# Arduino_Connection_PCB.net
KiCad netlist of a schematic drawn in EAGLE
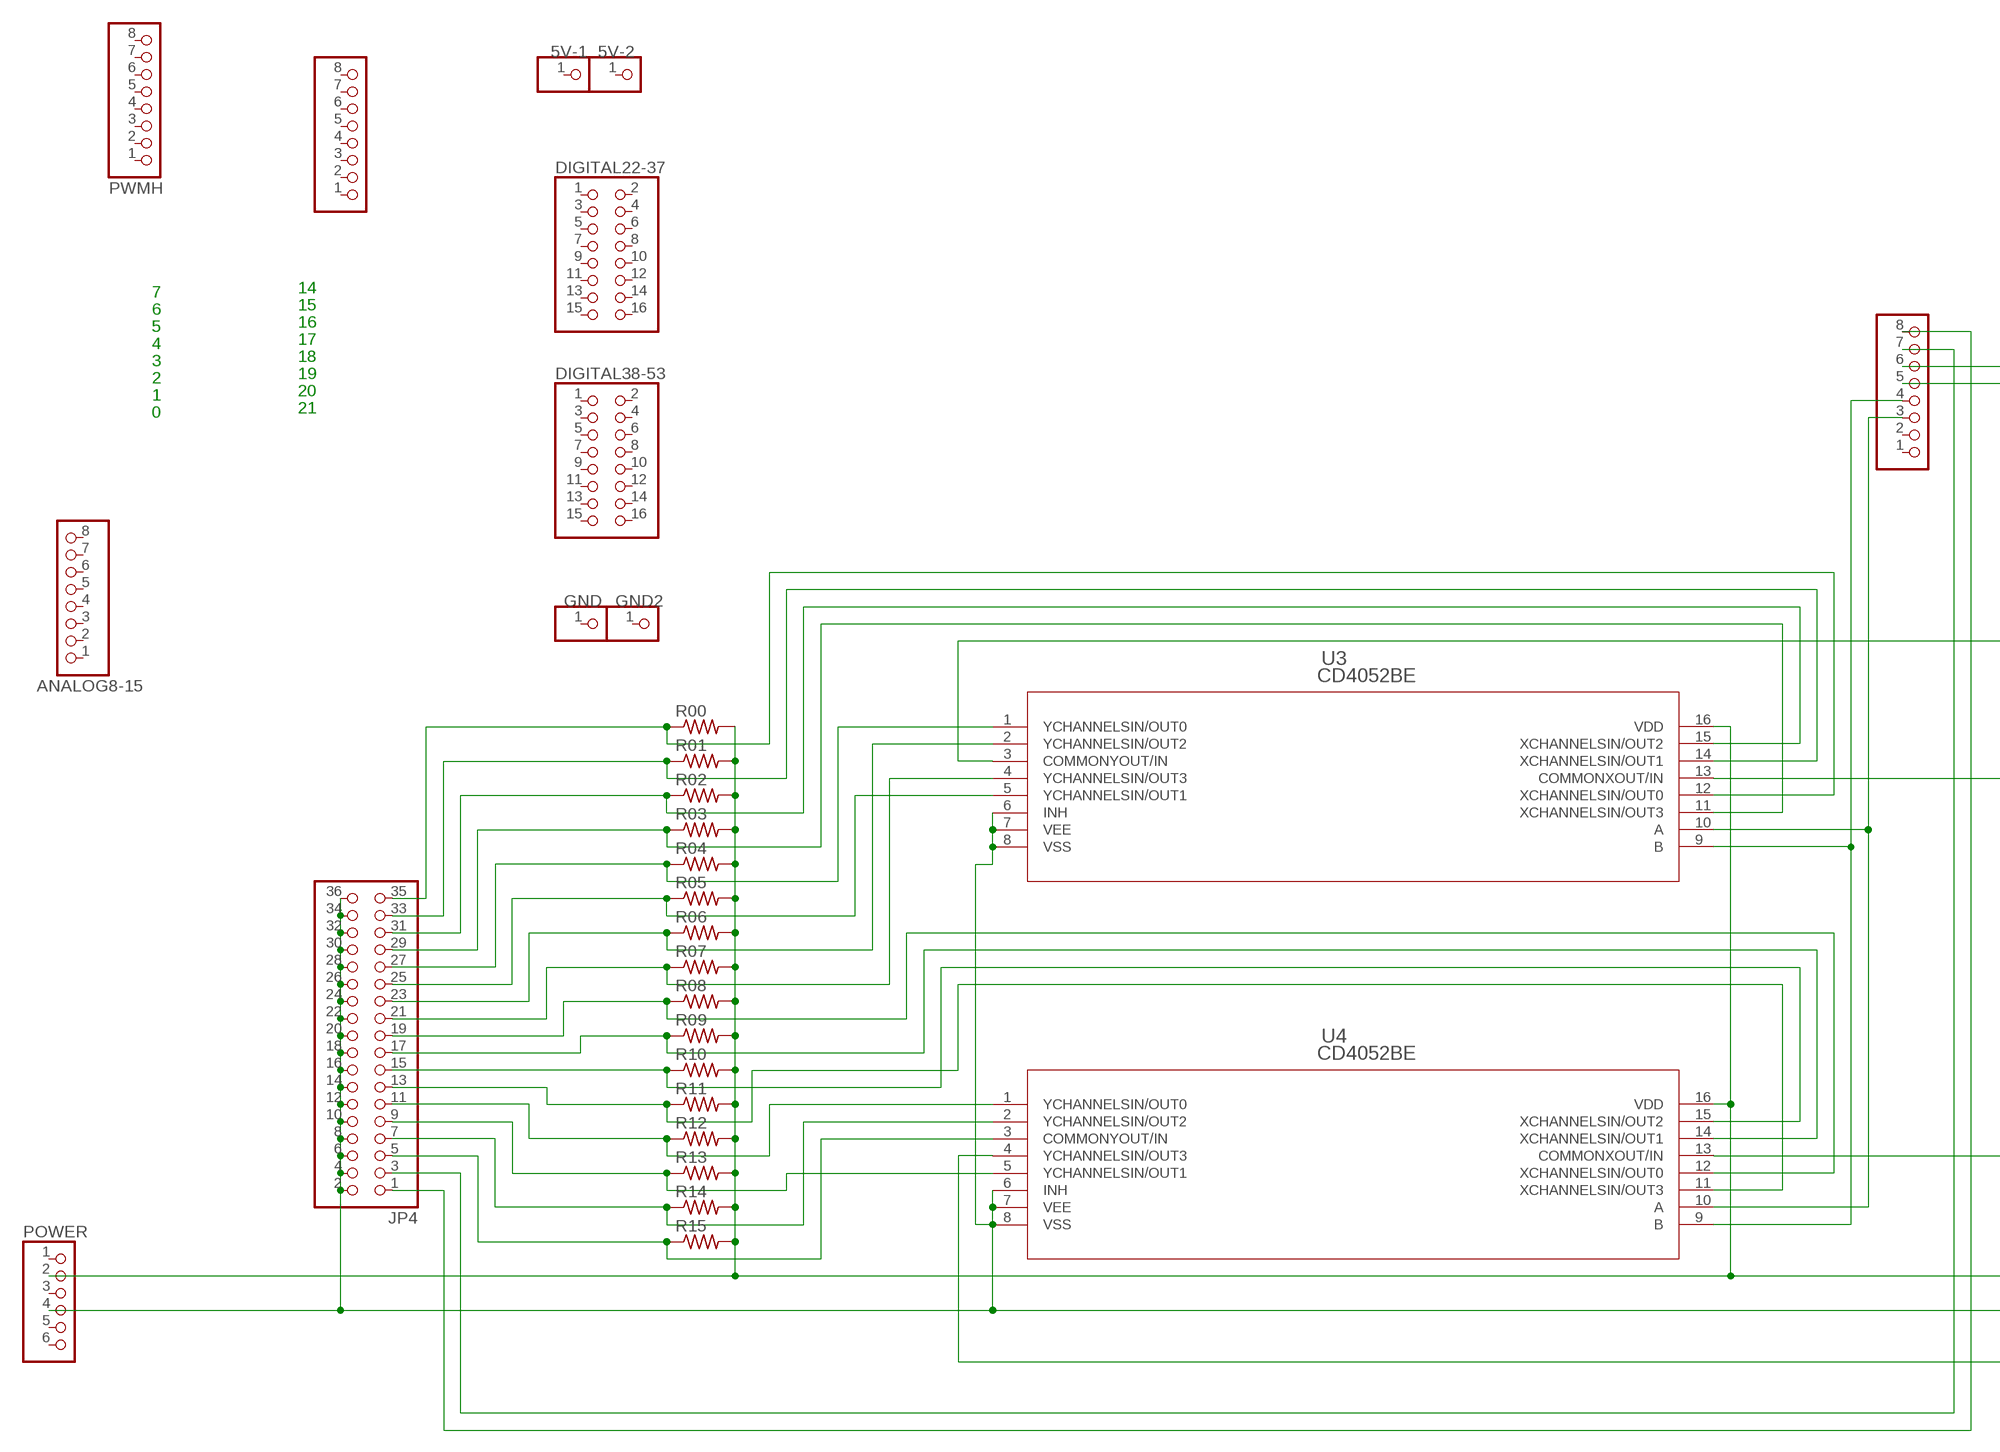
[diagram p0: schematic, sheet 1, part 1 of 2]
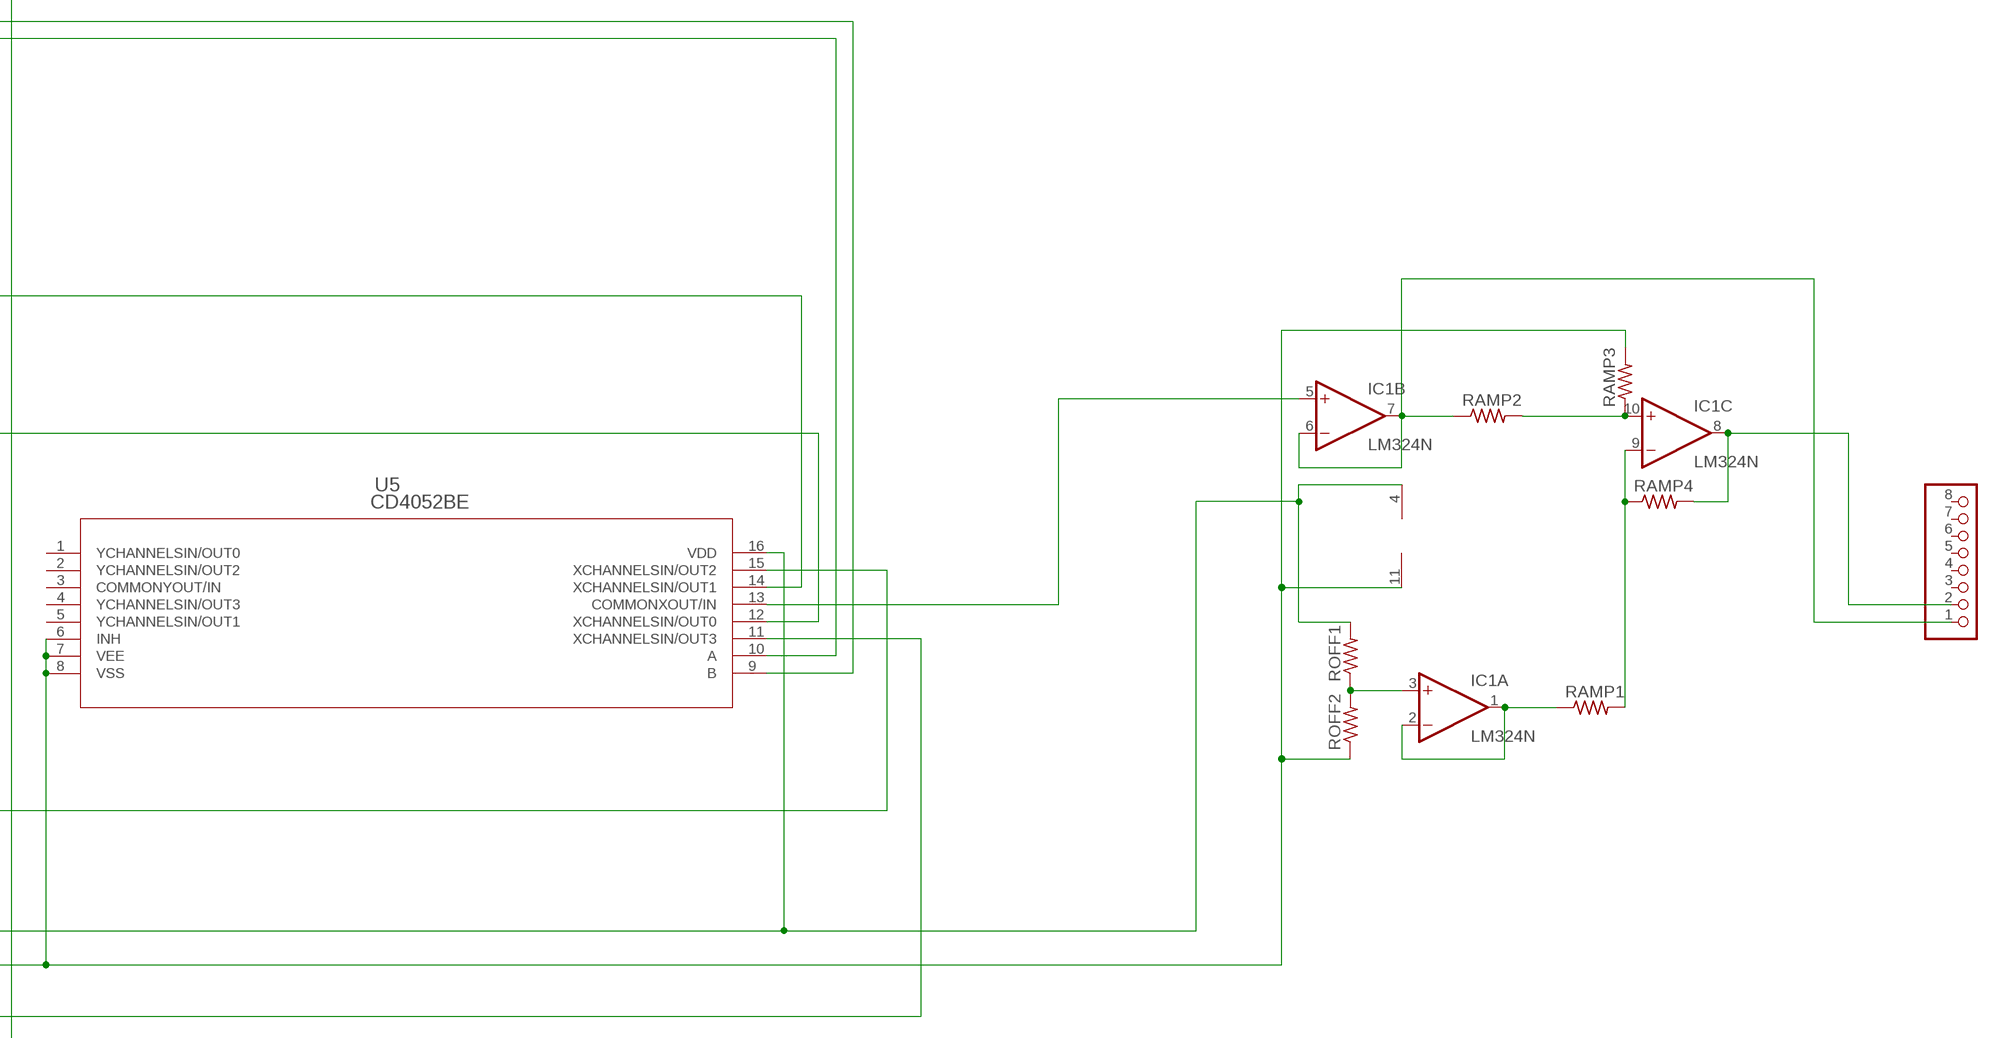
[diagram p1: schematic, sheet 1, part 2 of 2]

(export (version "E")
  (design (tool "Eeschema 10.0.6"))
  (components
    (comp (ref "5V-1")
      (value "PINHD-1X1")
      (footprint "eagle-import:1X01")
      (libsource (lib "eagle-import") (part "PINHD-1X1"))
    )
    (comp (ref "5V-2")
      (value "PINHD-1X1")
      (footprint "eagle-import:1X01")
      (libsource (lib "eagle-import") (part "PINHD-1X1"))
    )
    (comp (ref "ANALOG0-7")
      (value "PINHD-1X8")
      (footprint "eagle-import:1X08")
      (libsource (lib "eagle-import") (part "PINHD-1X8"))
    )
    (comp (ref "ANALOG8-15")
      (value "PINHD-1X8")
      (footprint "eagle-import:1X08")
      (libsource (lib "eagle-import") (part "PINHD-1X8"))
    )
    (comp (ref "COMMUNICATION")
      (value "PINHD-1X8")
      (footprint "eagle-import:1X08")
      (libsource (lib "eagle-import") (part "PINHD-1X8"))
    )
    (comp (ref "DIGITAL22-37")
      (value "PINHD-2X8")
      (footprint "eagle-import:2X08")
      (libsource (lib "eagle-import") (part "PINHD-2X8"))
    )
    (comp (ref "DIGITAL38-53")
      (value "PINHD-2X8")
      (footprint "eagle-import:2X08")
      (libsource (lib "eagle-import") (part "PINHD-2X8"))
    )
    (comp (ref "GND")
      (value "PINHD-1X1")
      (footprint "eagle-import:1X01")
      (libsource (lib "eagle-import") (part "PINHD-1X1"))
    )
    (comp (ref "GND2")
      (value "PINHD-1X1")
      (footprint "eagle-import:1X01")
      (libsource (lib "eagle-import") (part "PINHD-1X1"))
    )
    (comp (ref "IC1")
      (value "LM324N")
      (footprint "eagle-import:DIL14")
      (libsource (lib "eagle-import") (part "LM324N"))
    )
    (comp (ref "JP4")
      (value "PINHD-2X18/90")
      (footprint "eagle-import:2X18_90")
      (libsource (lib "eagle-import") (part "PINHD-2X18/90"))
    )
    (comp (ref "POWER")
      (value "PINHD-1X6")
      (footprint "eagle-import:1X06")
      (libsource (lib "eagle-import") (part "PINHD-1X6"))
    )
    (comp (ref "PWMH")
      (value "PINHD-1X8")
      (footprint "eagle-import:1X08")
      (libsource (lib "eagle-import") (part "PINHD-1X8"))
    )
    (comp (ref "PWML")
      (value "PINHD-1X8")
      (footprint "eagle-import:1X08")
      (libsource (lib "eagle-import") (part "PINHD-1X8"))
    )
    (comp (ref "R00")
      (value "R-US_0204/7")
      (footprint "eagle-import:0204_7")
      (libsource (lib "eagle-import") (part "R-US_0204/7"))
    )
    (comp (ref "R01")
      (value "R-US_0204/7")
      (footprint "eagle-import:0204_7")
      (libsource (lib "eagle-import") (part "R-US_0204/7"))
    )
    (comp (ref "R02")
      (value "R-US_0204/7")
      (footprint "eagle-import:0204_7")
      (libsource (lib "eagle-import") (part "R-US_0204/7"))
    )
    (comp (ref "R03")
      (value "R-US_0204/7")
      (footprint "eagle-import:0204_7")
      (libsource (lib "eagle-import") (part "R-US_0204/7"))
    )
    (comp (ref "R04")
      (value "R-US_0204/7")
      (footprint "eagle-import:0204_7")
      (libsource (lib "eagle-import") (part "R-US_0204/7"))
    )
    (comp (ref "R05")
      (value "R-US_0204/7")
      (footprint "eagle-import:0204_7")
      (libsource (lib "eagle-import") (part "R-US_0204/7"))
    )
    (comp (ref "R06")
      (value "R-US_0204/7")
      (footprint "eagle-import:0204_7")
      (libsource (lib "eagle-import") (part "R-US_0204/7"))
    )
    (comp (ref "R07")
      (value "R-US_0204/7")
      (footprint "eagle-import:0204_7")
      (libsource (lib "eagle-import") (part "R-US_0204/7"))
    )
    (comp (ref "R08")
      (value "R-US_0204/7")
      (footprint "eagle-import:0204_7")
      (libsource (lib "eagle-import") (part "R-US_0204/7"))
    )
    (comp (ref "R09")
      (value "R-US_0204/7")
      (footprint "eagle-import:0204_7")
      (libsource (lib "eagle-import") (part "R-US_0204/7"))
    )
    (comp (ref "R10")
      (value "R-US_0204/7")
      (footprint "eagle-import:0204_7")
      (libsource (lib "eagle-import") (part "R-US_0204/7"))
    )
    (comp (ref "R11")
      (value "R-US_0204/7")
      (footprint "eagle-import:0204_7")
      (libsource (lib "eagle-import") (part "R-US_0204/7"))
    )
    (comp (ref "R12")
      (value "R-US_0204/7")
      (footprint "eagle-import:0204_7")
      (libsource (lib "eagle-import") (part "R-US_0204/7"))
    )
    (comp (ref "R13")
      (value "R-US_0204/7")
      (footprint "eagle-import:0204_7")
      (libsource (lib "eagle-import") (part "R-US_0204/7"))
    )
    (comp (ref "R14")
      (value "R-US_0204/7")
      (footprint "eagle-import:0204_7")
      (libsource (lib "eagle-import") (part "R-US_0204/7"))
    )
    (comp (ref "R15")
      (value "R-US_0204/7")
      (footprint "eagle-import:0204_7")
      (libsource (lib "eagle-import") (part "R-US_0204/7"))
    )
    (comp (ref "RAMP1")
      (value "R-US_0204/7")
      (footprint "eagle-import:0204_7")
      (libsource (lib "eagle-import") (part "R-US_0204/7"))
    )
    (comp (ref "RAMP2")
      (value "R-US_0204/7")
      (footprint "eagle-import:0204_7")
      (libsource (lib "eagle-import") (part "R-US_0204/7"))
    )
    (comp (ref "RAMP3")
      (value "R-US_0204/7")
      (footprint "eagle-import:0204_7")
      (libsource (lib "eagle-import") (part "R-US_0204/7"))
    )
    (comp (ref "RAMP4")
      (value "R-US_0204/7")
      (footprint "eagle-import:0204_7")
      (libsource (lib "eagle-import") (part "R-US_0204/7"))
    )
    (comp (ref "ROFF1")
      (value "R-US_0204/7")
      (footprint "eagle-import:0204_7")
      (libsource (lib "eagle-import") (part "R-US_0204/7"))
    )
    (comp (ref "ROFF2")
      (value "R-US_0204/7")
      (footprint "eagle-import:0204_7")
      (libsource (lib "eagle-import") (part "R-US_0204/7"))
    )
    (comp (ref "U3")
      (value "CD4052BE")
      (footprint "eagle-import:N16")
      (libsource (lib "eagle-import") (part "CD4052BE"))
    )
    (comp (ref "U4")
      (value "CD4052BE")
      (footprint "eagle-import:N16")
      (libsource (lib "eagle-import") (part "CD4052BE"))
    )
    (comp (ref "U5")
      (value "CD4052BE")
      (footprint "eagle-import:N16")
      (libsource (lib "eagle-import") (part "CD4052BE"))
    )
  )
  (nets
    (net (code "1") (name "Net-(IC1A-+IN)") (class "Default")
      (node (ref "IC1") (pin "3") (pinfunction "+IN_3") (pintype "input"))
      (node (ref "ROFF1") (pin "1") (pinfunction "1_1") (pintype "passive"))
      (node (ref "ROFF2") (pin "2") (pinfunction "2_2") (pintype "passive"))
    )
    (net (code "2") (name "Net-(IC1A--IN)") (class "Default")
      (node (ref "IC1") (pin "1") (pinfunction "OUT_1") (pintype "output"))
      (node (ref "IC1") (pin "2") (pinfunction "-IN_2") (pintype "input"))
      (node (ref "RAMP1") (pin "1") (pinfunction "1_1") (pintype "passive"))
    )
    (net (code "3") (name "Net-(IC1B-+IN)") (class "Default")
      (node (ref "IC1") (pin "5") (pinfunction "+IN_5") (pintype "input"))
      (node (ref "U5") (pin "13") (pinfunction "COMMONXOUT/IN_13") (pintype "bidirectional"))
    )
    (net (code "4") (name "Net-(IC1B--IN)") (class "Default")
      (node (ref "ANALOG0-7") (pin "1") (pinfunction "1_1") (pintype "passive"))
      (node (ref "IC1") (pin "6") (pinfunction "-IN_6") (pintype "input"))
      (node (ref "IC1") (pin "7") (pinfunction "OUT_7") (pintype "output"))
      (node (ref "RAMP2") (pin "1") (pinfunction "1_1") (pintype "passive"))
    )
    (net (code "5") (name "Net-(IC1C-+IN)") (class "Default")
      (node (ref "IC1") (pin "10") (pinfunction "+IN_10") (pintype "input"))
      (node (ref "RAMP2") (pin "2") (pinfunction "2_2") (pintype "passive"))
      (node (ref "RAMP3") (pin "1") (pinfunction "1_1") (pintype "passive"))
    )
    (net (code "6") (name "Net-(IC1C--IN)") (class "Default")
      (node (ref "IC1") (pin "9") (pinfunction "-IN_9") (pintype "input"))
      (node (ref "RAMP1") (pin "2") (pinfunction "2_2") (pintype "passive"))
      (node (ref "RAMP4") (pin "1") (pinfunction "1_1") (pintype "passive"))
    )
    (net (code "7") (name "Net-(IC1C-OUT)") (class "Default")
      (node (ref "ANALOG0-7") (pin "2") (pinfunction "2_2") (pintype "passive"))
      (node (ref "IC1") (pin "8") (pinfunction "OUT_8") (pintype "output"))
      (node (ref "RAMP4") (pin "2") (pinfunction "2_2") (pintype "passive"))
    )
    (net (code "8") (name "Net-(IC1E-V+)") (class "Default")
      (node (ref "IC1") (pin "4") (pinfunction "V+_4") (pintype "power_in"))
      (node (ref "POWER") (pin "2") (pinfunction "2_2") (pintype "passive"))
      (node (ref "R00") (pin "2") (pinfunction "2_2") (pintype "passive"))
      (node (ref "R01") (pin "2") (pinfunction "2_2") (pintype "passive"))
      (node (ref "R02") (pin "2") (pinfunction "2_2") (pintype "passive"))
      (node (ref "R03") (pin "2") (pinfunction "2_2") (pintype "passive"))
      (node (ref "R04") (pin "2") (pinfunction "2_2") (pintype "passive"))
      (node (ref "R05") (pin "2") (pinfunction "2_2") (pintype "passive"))
      (node (ref "R06") (pin "2") (pinfunction "2_2") (pintype "passive"))
      (node (ref "R07") (pin "2") (pinfunction "2_2") (pintype "passive"))
      (node (ref "R08") (pin "2") (pinfunction "2_2") (pintype "passive"))
      (node (ref "R09") (pin "2") (pinfunction "2_2") (pintype "passive"))
      (node (ref "R10") (pin "2") (pinfunction "2_2") (pintype "passive"))
      (node (ref "R11") (pin "2") (pinfunction "2_2") (pintype "passive"))
      (node (ref "R12") (pin "2") (pinfunction "2_2") (pintype "passive"))
      (node (ref "R13") (pin "2") (pinfunction "2_2") (pintype "passive"))
      (node (ref "R14") (pin "2") (pinfunction "2_2") (pintype "passive"))
      (node (ref "R15") (pin "2") (pinfunction "2_2") (pintype "passive"))
      (node (ref "ROFF1") (pin "2") (pinfunction "2_2") (pintype "passive"))
      (node (ref "U3") (pin "16") (pinfunction "VDD_16") (pintype "power_in"))
      (node (ref "U4") (pin "16") (pinfunction "VDD_16") (pintype "power_in"))
      (node (ref "U5") (pin "16") (pinfunction "VDD_16") (pintype "power_in"))
    )
    (net (code "9") (name "Net-(IC1E-V-)") (class "Default")
      (node (ref "IC1") (pin "11") (pinfunction "V-_11") (pintype "power_in"))
      (node (ref "JP4") (pin "10") (pinfunction "10_10") (pintype "passive"))
      (node (ref "JP4") (pin "12") (pinfunction "12_12") (pintype "passive"))
      (node (ref "JP4") (pin "14") (pinfunction "14_14") (pintype "passive"))
      (node (ref "JP4") (pin "16") (pinfunction "16_16") (pintype "passive"))
      (node (ref "JP4") (pin "18") (pinfunction "18_18") (pintype "passive"))
      (node (ref "JP4") (pin "2") (pinfunction "2_2") (pintype "passive"))
      (node (ref "JP4") (pin "20") (pinfunction "20_20") (pintype "passive"))
      (node (ref "JP4") (pin "22") (pinfunction "22_22") (pintype "passive"))
      (node (ref "JP4") (pin "24") (pinfunction "24_24") (pintype "passive"))
      (node (ref "JP4") (pin "26") (pinfunction "26_26") (pintype "passive"))
      (node (ref "JP4") (pin "28") (pinfunction "28_28") (pintype "passive"))
      (node (ref "JP4") (pin "30") (pinfunction "30_30") (pintype "passive"))
      (node (ref "JP4") (pin "32") (pinfunction "32_32") (pintype "passive"))
      (node (ref "JP4") (pin "34") (pinfunction "34_34") (pintype "passive"))
      (node (ref "JP4") (pin "36") (pinfunction "36_36") (pintype "passive"))
      (node (ref "JP4") (pin "4") (pinfunction "4_4") (pintype "passive"))
      (node (ref "JP4") (pin "6") (pinfunction "6_6") (pintype "passive"))
      (node (ref "JP4") (pin "8") (pinfunction "8_8") (pintype "passive"))
      (node (ref "POWER") (pin "4") (pinfunction "4_4") (pintype "passive"))
      (node (ref "RAMP3") (pin "2") (pinfunction "2_2") (pintype "passive"))
      (node (ref "ROFF2") (pin "1") (pinfunction "1_1") (pintype "passive"))
      (node (ref "U3") (pin "6") (pinfunction "INH_6") (pintype "passive"))
      (node (ref "U3") (pin "7") (pinfunction "VEE_7") (pintype "power_in"))
      (node (ref "U3") (pin "8") (pinfunction "VSS_8") (pintype "power_in"))
      (node (ref "U4") (pin "6") (pinfunction "INH_6") (pintype "passive"))
      (node (ref "U4") (pin "7") (pinfunction "VEE_7") (pintype "power_in"))
      (node (ref "U4") (pin "8") (pinfunction "VSS_8") (pintype "power_in"))
      (node (ref "U5") (pin "6") (pinfunction "INH_6") (pintype "passive"))
      (node (ref "U5") (pin "7") (pinfunction "VEE_7") (pintype "power_in"))
      (node (ref "U5") (pin "8") (pinfunction "VSS_8") (pintype "power_in"))
    )
    (net (code "10") (name "Net-(JP4-Pad1)") (class "Default")
      (node (ref "JP4") (pin "1") (pinfunction "1_1") (pintype "passive"))
      (node (ref "PWML") (pin "8") (pinfunction "8_8") (pintype "passive"))
    )
    (net (code "11") (name "Net-(JP4-Pad3)") (class "Default")
      (node (ref "JP4") (pin "3") (pinfunction "3_3") (pintype "passive"))
      (node (ref "PWML") (pin "7") (pinfunction "7_7") (pintype "passive"))
    )
    (net (code "12") (name "Net-(U3-A)") (class "Default")
      (node (ref "PWML") (pin "3") (pinfunction "3_3") (pintype "passive"))
      (node (ref "U3") (pin "10") (pinfunction "A_10") (pintype "passive"))
      (node (ref "U4") (pin "10") (pinfunction "A_10") (pintype "passive"))
    )
    (net (code "13") (name "Net-(U3-B)") (class "Default")
      (node (ref "PWML") (pin "4") (pinfunction "4_4") (pintype "passive"))
      (node (ref "U3") (pin "9") (pinfunction "B_9") (pintype "passive"))
      (node (ref "U4") (pin "9") (pinfunction "B_9") (pintype "passive"))
    )
    (net (code "14") (name "Net-(U3-COMMONXOUT{slash}IN)") (class "Default")
      (node (ref "U3") (pin "13") (pinfunction "COMMONXOUT/IN_13") (pintype "bidirectional"))
      (node (ref "U5") (pin "12") (pinfunction "XCHANNELSIN/OUT0_12") (pintype "bidirectional"))
    )
    (net (code "15") (name "Net-(U3-COMMONYOUT{slash}IN)") (class "Default")
      (node (ref "U3") (pin "3") (pinfunction "COMMONYOUT/IN_3") (pintype "bidirectional"))
      (node (ref "U5") (pin "14") (pinfunction "XCHANNELSIN/OUT1_14") (pintype "bidirectional"))
    )
    (net (code "16") (name "Net-(U3-XCHANNELSIN{slash}OUT0)") (class "Default")
      (node (ref "JP4") (pin "35") (pinfunction "35_35") (pintype "passive"))
      (node (ref "R00") (pin "1") (pinfunction "1_1") (pintype "passive"))
      (node (ref "U3") (pin "12") (pinfunction "XCHANNELSIN/OUT0_12") (pintype "bidirectional"))
    )
    (net (code "17") (name "Net-(U3-XCHANNELSIN{slash}OUT1)") (class "Default")
      (node (ref "JP4") (pin "33") (pinfunction "33_33") (pintype "passive"))
      (node (ref "R01") (pin "1") (pinfunction "1_1") (pintype "passive"))
      (node (ref "U3") (pin "14") (pinfunction "XCHANNELSIN/OUT1_14") (pintype "bidirectional"))
    )
    (net (code "18") (name "Net-(U3-XCHANNELSIN{slash}OUT2)") (class "Default")
      (node (ref "JP4") (pin "31") (pinfunction "31_31") (pintype "passive"))
      (node (ref "R02") (pin "1") (pinfunction "1_1") (pintype "passive"))
      (node (ref "U3") (pin "15") (pinfunction "XCHANNELSIN/OUT2_15") (pintype "bidirectional"))
    )
    (net (code "19") (name "Net-(U3-XCHANNELSIN{slash}OUT3)") (class "Default")
      (node (ref "JP4") (pin "29") (pinfunction "29_29") (pintype "passive"))
      (node (ref "R03") (pin "1") (pinfunction "1_1") (pintype "passive"))
      (node (ref "U3") (pin "11") (pinfunction "XCHANNELSIN/OUT3_11") (pintype "bidirectional"))
    )
    (net (code "20") (name "Net-(U3-YCHANNELSIN{slash}OUT0)") (class "Default")
      (node (ref "JP4") (pin "27") (pinfunction "27_27") (pintype "passive"))
      (node (ref "R04") (pin "1") (pinfunction "1_1") (pintype "passive"))
      (node (ref "U3") (pin "1") (pinfunction "YCHANNELSIN/OUT0_1") (pintype "bidirectional"))
    )
    (net (code "21") (name "Net-(U3-YCHANNELSIN{slash}OUT1)") (class "Default")
      (node (ref "JP4") (pin "25") (pinfunction "25_25") (pintype "passive"))
      (node (ref "R05") (pin "1") (pinfunction "1_1") (pintype "passive"))
      (node (ref "U3") (pin "5") (pinfunction "YCHANNELSIN/OUT1_5") (pintype "bidirectional"))
    )
    (net (code "22") (name "Net-(U3-YCHANNELSIN{slash}OUT2)") (class "Default")
      (node (ref "JP4") (pin "23") (pinfunction "23_23") (pintype "passive"))
      (node (ref "R06") (pin "1") (pinfunction "1_1") (pintype "passive"))
      (node (ref "U3") (pin "2") (pinfunction "YCHANNELSIN/OUT2_2") (pintype "bidirectional"))
    )
    (net (code "23") (name "Net-(U3-YCHANNELSIN{slash}OUT3)") (class "Default")
      (node (ref "JP4") (pin "21") (pinfunction "21_21") (pintype "passive"))
      (node (ref "R07") (pin "1") (pinfunction "1_1") (pintype "passive"))
      (node (ref "U3") (pin "4") (pinfunction "YCHANNELSIN/OUT3_4") (pintype "bidirectional"))
    )
    (net (code "24") (name "Net-(U4-COMMONXOUT{slash}IN)") (class "Default")
      (node (ref "U4") (pin "13") (pinfunction "COMMONXOUT/IN_13") (pintype "bidirectional"))
      (node (ref "U5") (pin "15") (pinfunction "XCHANNELSIN/OUT2_15") (pintype "bidirectional"))
    )
    (net (code "25") (name "Net-(U4-COMMONYOUT{slash}IN)") (class "Default")
      (node (ref "JP4") (pin "5") (pinfunction "5_5") (pintype "passive"))
      (node (ref "R15") (pin "1") (pinfunction "1_1") (pintype "passive"))
      (node (ref "U4") (pin "3") (pinfunction "COMMONYOUT/IN_3") (pintype "bidirectional"))
    )
    (net (code "26") (name "Net-(U4-XCHANNELSIN{slash}OUT0)") (class "Default")
      (node (ref "JP4") (pin "19") (pinfunction "19_19") (pintype "passive"))
      (node (ref "R08") (pin "1") (pinfunction "1_1") (pintype "passive"))
      (node (ref "U4") (pin "12") (pinfunction "XCHANNELSIN/OUT0_12") (pintype "bidirectional"))
    )
    (net (code "27") (name "Net-(U4-XCHANNELSIN{slash}OUT1)") (class "Default")
      (node (ref "JP4") (pin "17") (pinfunction "17_17") (pintype "passive"))
      (node (ref "R09") (pin "1") (pinfunction "1_1") (pintype "passive"))
      (node (ref "U4") (pin "14") (pinfunction "XCHANNELSIN/OUT1_14") (pintype "bidirectional"))
    )
    (net (code "28") (name "Net-(U4-XCHANNELSIN{slash}OUT2)") (class "Default")
      (node (ref "JP4") (pin "15") (pinfunction "15_15") (pintype "passive"))
      (node (ref "R10") (pin "1") (pinfunction "1_1") (pintype "passive"))
      (node (ref "U4") (pin "15") (pinfunction "XCHANNELSIN/OUT2_15") (pintype "bidirectional"))
    )
    (net (code "29") (name "Net-(U4-XCHANNELSIN{slash}OUT3)") (class "Default")
      (node (ref "JP4") (pin "13") (pinfunction "13_13") (pintype "passive"))
      (node (ref "R11") (pin "1") (pinfunction "1_1") (pintype "passive"))
      (node (ref "U4") (pin "11") (pinfunction "XCHANNELSIN/OUT3_11") (pintype "bidirectional"))
    )
    (net (code "30") (name "Net-(U4-YCHANNELSIN{slash}OUT0)") (class "Default")
      (node (ref "JP4") (pin "11") (pinfunction "11_11") (pintype "passive"))
      (node (ref "R12") (pin "1") (pinfunction "1_1") (pintype "passive"))
      (node (ref "U4") (pin "1") (pinfunction "YCHANNELSIN/OUT0_1") (pintype "bidirectional"))
    )
    (net (code "31") (name "Net-(U4-YCHANNELSIN{slash}OUT1)") (class "Default")
      (node (ref "JP4") (pin "9") (pinfunction "9_9") (pintype "passive"))
      (node (ref "R13") (pin "1") (pinfunction "1_1") (pintype "passive"))
      (node (ref "U4") (pin "5") (pinfunction "YCHANNELSIN/OUT1_5") (pintype "bidirectional"))
    )
    (net (code "32") (name "Net-(U4-YCHANNELSIN{slash}OUT2)") (class "Default")
      (node (ref "JP4") (pin "7") (pinfunction "7_7") (pintype "passive"))
      (node (ref "R14") (pin "1") (pinfunction "1_1") (pintype "passive"))
      (node (ref "U4") (pin "2") (pinfunction "YCHANNELSIN/OUT2_2") (pintype "bidirectional"))
    )
    (net (code "33") (name "Net-(U4-YCHANNELSIN{slash}OUT3)") (class "Default")
      (node (ref "U4") (pin "4") (pinfunction "YCHANNELSIN/OUT3_4") (pintype "bidirectional"))
      (node (ref "U5") (pin "11") (pinfunction "XCHANNELSIN/OUT3_11") (pintype "bidirectional"))
    )
    (net (code "34") (name "Net-(U5-A)") (class "Default")
      (node (ref "PWML") (pin "5") (pinfunction "5_5") (pintype "passive"))
      (node (ref "U5") (pin "10") (pinfunction "A_10") (pintype "passive"))
    )
    (net (code "35") (name "Net-(U5-B)") (class "Default")
      (node (ref "PWML") (pin "6") (pinfunction "6_6") (pintype "passive"))
      (node (ref "U5") (pin "9") (pinfunction "B_9") (pintype "passive"))
    )
    (net (code "36") (name "unconnected-(5V-1-Pad1)") (class "Default")
      (node (ref "5V-1") (pin "1") (pinfunction "1_1") (pintype "passive"))
    )
    (net (code "37") (name "unconnected-(5V-2-Pad1)") (class "Default")
      (node (ref "5V-2") (pin "1") (pinfunction "1_1") (pintype "passive"))
    )
    (net (code "38") (name "unconnected-(ANALOG0-7-Pad3)") (class "Default")
      (node (ref "ANALOG0-7") (pin "3") (pinfunction "3_3") (pintype "passive"))
    )
    (net (code "39") (name "unconnected-(ANALOG0-7-Pad4)") (class "Default")
      (node (ref "ANALOG0-7") (pin "4") (pinfunction "4_4") (pintype "passive"))
    )
    (net (code "40") (name "unconnected-(ANALOG0-7-Pad5)") (class "Default")
      (node (ref "ANALOG0-7") (pin "5") (pinfunction "5_5") (pintype "passive"))
    )
    (net (code "41") (name "unconnected-(ANALOG0-7-Pad6)") (class "Default")
      (node (ref "ANALOG0-7") (pin "6") (pinfunction "6_6") (pintype "passive"))
    )
    (net (code "42") (name "unconnected-(ANALOG0-7-Pad7)") (class "Default")
      (node (ref "ANALOG0-7") (pin "7") (pinfunction "7_7") (pintype "passive"))
    )
    (net (code "43") (name "unconnected-(ANALOG0-7-Pad8)") (class "Default")
      (node (ref "ANALOG0-7") (pin "8") (pinfunction "8_8") (pintype "passive"))
    )
    (net (code "44") (name "unconnected-(ANALOG8-15-Pad1)") (class "Default")
      (node (ref "ANALOG8-15") (pin "1") (pinfunction "1_1") (pintype "passive"))
    )
    (net (code "45") (name "unconnected-(ANALOG8-15-Pad2)") (class "Default")
      (node (ref "ANALOG8-15") (pin "2") (pinfunction "2_2") (pintype "passive"))
    )
    (net (code "46") (name "unconnected-(ANALOG8-15-Pad3)") (class "Default")
      (node (ref "ANALOG8-15") (pin "3") (pinfunction "3_3") (pintype "passive"))
    )
    (net (code "47") (name "unconnected-(ANALOG8-15-Pad4)") (class "Default")
      (node (ref "ANALOG8-15") (pin "4") (pinfunction "4_4") (pintype "passive"))
    )
    (net (code "48") (name "unconnected-(ANALOG8-15-Pad5)") (class "Default")
      (node (ref "ANALOG8-15") (pin "5") (pinfunction "5_5") (pintype "passive"))
    )
    (net (code "49") (name "unconnected-(ANALOG8-15-Pad6)") (class "Default")
      (node (ref "ANALOG8-15") (pin "6") (pinfunction "6_6") (pintype "passive"))
    )
    (net (code "50") (name "unconnected-(ANALOG8-15-Pad7)") (class "Default")
      (node (ref "ANALOG8-15") (pin "7") (pinfunction "7_7") (pintype "passive"))
    )
    (net (code "51") (name "unconnected-(ANALOG8-15-Pad8)") (class "Default")
      (node (ref "ANALOG8-15") (pin "8") (pinfunction "8_8") (pintype "passive"))
    )
    (net (code "52") (name "unconnected-(COMMUNICATION-Pad1)") (class "Default")
      (node (ref "COMMUNICATION") (pin "1") (pinfunction "1_1") (pintype "passive"))
    )
    (net (code "53") (name "unconnected-(COMMUNICATION-Pad2)") (class "Default")
      (node (ref "COMMUNICATION") (pin "2") (pinfunction "2_2") (pintype "passive"))
    )
    (net (code "54") (name "unconnected-(COMMUNICATION-Pad3)") (class "Default")
      (node (ref "COMMUNICATION") (pin "3") (pinfunction "3_3") (pintype "passive"))
    )
    (net (code "55") (name "unconnected-(COMMUNICATION-Pad4)") (class "Default")
      (node (ref "COMMUNICATION") (pin "4") (pinfunction "4_4") (pintype "passive"))
    )
    (net (code "56") (name "unconnected-(COMMUNICATION-Pad5)") (class "Default")
      (node (ref "COMMUNICATION") (pin "5") (pinfunction "5_5") (pintype "passive"))
    )
    (net (code "57") (name "unconnected-(COMMUNICATION-Pad6)") (class "Default")
      (node (ref "COMMUNICATION") (pin "6") (pinfunction "6_6") (pintype "passive"))
    )
    (net (code "58") (name "unconnected-(COMMUNICATION-Pad7)") (class "Default")
      (node (ref "COMMUNICATION") (pin "7") (pinfunction "7_7") (pintype "passive"))
    )
    (net (code "59") (name "unconnected-(COMMUNICATION-Pad8)") (class "Default")
      (node (ref "COMMUNICATION") (pin "8") (pinfunction "8_8") (pintype "passive"))
    )
    (net (code "60") (name "unconnected-(DIGITAL22-37-Pad1)") (class "Default")
      (node (ref "DIGITAL22-37") (pin "1") (pinfunction "1_1") (pintype "passive"))
    )
    (net (code "61") (name "unconnected-(DIGITAL22-37-Pad2)") (class "Default")
      (node (ref "DIGITAL22-37") (pin "2") (pinfunction "2_2") (pintype "passive"))
    )
    (net (code "62") (name "unconnected-(DIGITAL22-37-Pad3)") (class "Default")
      (node (ref "DIGITAL22-37") (pin "3") (pinfunction "3_3") (pintype "passive"))
    )
    (net (code "63") (name "unconnected-(DIGITAL22-37-Pad4)") (class "Default")
      (node (ref "DIGITAL22-37") (pin "4") (pinfunction "4_4") (pintype "passive"))
    )
    (net (code "64") (name "unconnected-(DIGITAL22-37-Pad5)") (class "Default")
      (node (ref "DIGITAL22-37") (pin "5") (pinfunction "5_5") (pintype "passive"))
    )
    (net (code "65") (name "unconnected-(DIGITAL22-37-Pad6)") (class "Default")
      (node (ref "DIGITAL22-37") (pin "6") (pinfunction "6_6") (pintype "passive"))
    )
    (net (code "66") (name "unconnected-(DIGITAL22-37-Pad7)") (class "Default")
      (node (ref "DIGITAL22-37") (pin "7") (pinfunction "7_7") (pintype "passive"))
    )
    (net (code "67") (name "unconnected-(DIGITAL22-37-Pad8)") (class "Default")
      (node (ref "DIGITAL22-37") (pin "8") (pinfunction "8_8") (pintype "passive"))
    )
    (net (code "68") (name "unconnected-(DIGITAL22-37-Pad9)") (class "Default")
      (node (ref "DIGITAL22-37") (pin "9") (pinfunction "9_9") (pintype "passive"))
    )
    (net (code "69") (name "unconnected-(DIGITAL22-37-Pad10)") (class "Default")
      (node (ref "DIGITAL22-37") (pin "10") (pinfunction "10_10") (pintype "passive"))
    )
    (net (code "70") (name "unconnected-(DIGITAL22-37-Pad11)") (class "Default")
      (node (ref "DIGITAL22-37") (pin "11") (pinfunction "11_11") (pintype "passive"))
    )
    (net (code "71") (name "unconnected-(DIGITAL22-37-Pad12)") (class "Default")
      (node (ref "DIGITAL22-37") (pin "12") (pinfunction "12_12") (pintype "passive"))
    )
    (net (code "72") (name "unconnected-(DIGITAL22-37-Pad13)") (class "Default")
      (node (ref "DIGITAL22-37") (pin "13") (pinfunction "13_13") (pintype "passive"))
    )
    (net (code "73") (name "unconnected-(DIGITAL22-37-Pad14)") (class "Default")
      (node (ref "DIGITAL22-37") (pin "14") (pinfunction "14_14") (pintype "passive"))
    )
    (net (code "74") (name "unconnected-(DIGITAL22-37-Pad15)") (class "Default")
      (node (ref "DIGITAL22-37") (pin "15") (pinfunction "15_15") (pintype "passive"))
    )
    (net (code "75") (name "unconnected-(DIGITAL22-37-Pad16)") (class "Default")
      (node (ref "DIGITAL22-37") (pin "16") (pinfunction "16_16") (pintype "passive"))
    )
    (net (code "76") (name "unconnected-(DIGITAL38-53-Pad1)") (class "Default")
      (node (ref "DIGITAL38-53") (pin "1") (pinfunction "1_1") (pintype "passive"))
    )
    (net (code "77") (name "unconnected-(DIGITAL38-53-Pad2)") (class "Default")
      (node (ref "DIGITAL38-53") (pin "2") (pinfunction "2_2") (pintype "passive"))
    )
    (net (code "78") (name "unconnected-(DIGITAL38-53-Pad3)") (class "Default")
      (node (ref "DIGITAL38-53") (pin "3") (pinfunction "3_3") (pintype "passive"))
    )
    (net (code "79") (name "unconnected-(DIGITAL38-53-Pad4)") (class "Default")
      (node (ref "DIGITAL38-53") (pin "4") (pinfunction "4_4") (pintype "passive"))
    )
    (net (code "80") (name "unconnected-(DIGITAL38-53-Pad5)") (class "Default")
      (node (ref "DIGITAL38-53") (pin "5") (pinfunction "5_5") (pintype "passive"))
    )
    (net (code "81") (name "unconnected-(DIGITAL38-53-Pad6)") (class "Default")
      (node (ref "DIGITAL38-53") (pin "6") (pinfunction "6_6") (pintype "passive"))
    )
    (net (code "82") (name "unconnected-(DIGITAL38-53-Pad7)") (class "Default")
      (node (ref "DIGITAL38-53") (pin "7") (pinfunction "7_7") (pintype "passive"))
    )
    (net (code "83") (name "unconnected-(DIGITAL38-53-Pad8)") (class "Default")
      (node (ref "DIGITAL38-53") (pin "8") (pinfunction "8_8") (pintype "passive"))
    )
    (net (code "84") (name "unconnected-(DIGITAL38-53-Pad9)") (class "Default")
      (node (ref "DIGITAL38-53") (pin "9") (pinfunction "9_9") (pintype "passive"))
    )
    (net (code "85") (name "unconnected-(DIGITAL38-53-Pad10)") (class "Default")
      (node (ref "DIGITAL38-53") (pin "10") (pinfunction "10_10") (pintype "passive"))
    )
    (net (code "86") (name "unconnected-(DIGITAL38-53-Pad11)") (class "Default")
      (node (ref "DIGITAL38-53") (pin "11") (pinfunction "11_11") (pintype "passive"))
    )
    (net (code "87") (name "unconnected-(DIGITAL38-53-Pad12)") (class "Default")
      (node (ref "DIGITAL38-53") (pin "12") (pinfunction "12_12") (pintype "passive"))
    )
    (net (code "88") (name "unconnected-(DIGITAL38-53-Pad13)") (class "Default")
      (node (ref "DIGITAL38-53") (pin "13") (pinfunction "13_13") (pintype "passive"))
    )
    (net (code "89") (name "unconnected-(DIGITAL38-53-Pad14)") (class "Default")
      (node (ref "DIGITAL38-53") (pin "14") (pinfunction "14_14") (pintype "passive"))
    )
    (net (code "90") (name "unconnected-(DIGITAL38-53-Pad15)") (class "Default")
      (node (ref "DIGITAL38-53") (pin "15") (pinfunction "15_15") (pintype "passive"))
    )
    (net (code "91") (name "unconnected-(DIGITAL38-53-Pad16)") (class "Default")
      (node (ref "DIGITAL38-53") (pin "16") (pinfunction "16_16") (pintype "passive"))
    )
    (net (code "92") (name "unconnected-(GND-Pad1)") (class "Default")
      (node (ref "GND") (pin "1") (pinfunction "1_1") (pintype "passive"))
    )
    (net (code "93") (name "unconnected-(GND2-Pad1)") (class "Default")
      (node (ref "GND2") (pin "1") (pinfunction "1_1") (pintype "passive"))
    )
    (net (code "94") (name "unconnected-(POWER-Pad1)") (class "Default")
      (node (ref "POWER") (pin "1") (pinfunction "1_1") (pintype "passive"))
    )
    (net (code "95") (name "unconnected-(POWER-Pad3)") (class "Default")
      (node (ref "POWER") (pin "3") (pinfunction "3_3") (pintype "passive"))
    )
    (net (code "96") (name "unconnected-(POWER-Pad5)") (class "Default")
      (node (ref "POWER") (pin "5") (pinfunction "5_5") (pintype "passive"))
    )
    (net (code "97") (name "unconnected-(POWER-Pad6)") (class "Default")
      (node (ref "POWER") (pin "6") (pinfunction "6_6") (pintype "passive"))
    )
    (net (code "98") (name "unconnected-(PWMH-Pad1)") (class "Default")
      (node (ref "PWMH") (pin "1") (pinfunction "1_1") (pintype "passive"))
    )
    (net (code "99") (name "unconnected-(PWMH-Pad2)") (class "Default")
      (node (ref "PWMH") (pin "2") (pinfunction "2_2") (pintype "passive"))
    )
    (net (code "100") (name "unconnected-(PWMH-Pad3)") (class "Default")
      (node (ref "PWMH") (pin "3") (pinfunction "3_3") (pintype "passive"))
    )
    (net (code "101") (name "unconnected-(PWMH-Pad4)") (class "Default")
      (node (ref "PWMH") (pin "4") (pinfunction "4_4") (pintype "passive"))
    )
    (net (code "102") (name "unconnected-(PWMH-Pad5)") (class "Default")
      (node (ref "PWMH") (pin "5") (pinfunction "5_5") (pintype "passive"))
    )
    (net (code "103") (name "unconnected-(PWMH-Pad6)") (class "Default")
      (node (ref "PWMH") (pin "6") (pinfunction "6_6") (pintype "passive"))
    )
    (net (code "104") (name "unconnected-(PWMH-Pad7)") (class "Default")
      (node (ref "PWMH") (pin "7") (pinfunction "7_7") (pintype "passive"))
    )
    (net (code "105") (name "unconnected-(PWMH-Pad8)") (class "Default")
      (node (ref "PWMH") (pin "8") (pinfunction "8_8") (pintype "passive"))
    )
    (net (code "106") (name "unconnected-(PWML-Pad1)") (class "Default")
      (node (ref "PWML") (pin "1") (pinfunction "1_1") (pintype "passive"))
    )
    (net (code "107") (name "unconnected-(PWML-Pad2)") (class "Default")
      (node (ref "PWML") (pin "2") (pinfunction "2_2") (pintype "passive"))
    )
    (net (code "108") (name "unconnected-(U5-COMMONYOUT{slash}IN-Pad3)") (class "Default")
      (node (ref "U5") (pin "3") (pinfunction "COMMONYOUT/IN_3") (pintype "bidirectional"))
    )
    (net (code "109") (name "unconnected-(U5-YCHANNELSIN{slash}OUT0-Pad1)") (class "Default")
      (node (ref "U5") (pin "1") (pinfunction "YCHANNELSIN/OUT0_1") (pintype "bidirectional"))
    )
    (net (code "110") (name "unconnected-(U5-YCHANNELSIN{slash}OUT1-Pad5)") (class "Default")
      (node (ref "U5") (pin "5") (pinfunction "YCHANNELSIN/OUT1_5") (pintype "bidirectional"))
    )
    (net (code "111") (name "unconnected-(U5-YCHANNELSIN{slash}OUT2-Pad2)") (class "Default")
      (node (ref "U5") (pin "2") (pinfunction "YCHANNELSIN/OUT2_2") (pintype "bidirectional"))
    )
    (net (code "112") (name "unconnected-(U5-YCHANNELSIN{slash}OUT3-Pad4)") (class "Default")
      (node (ref "U5") (pin "4") (pinfunction "YCHANNELSIN/OUT3_4") (pintype "bidirectional"))
    )
  )
)
